# BtPluggy.net
KiCad netlist of a schematic drawn in EasyEDA Pro
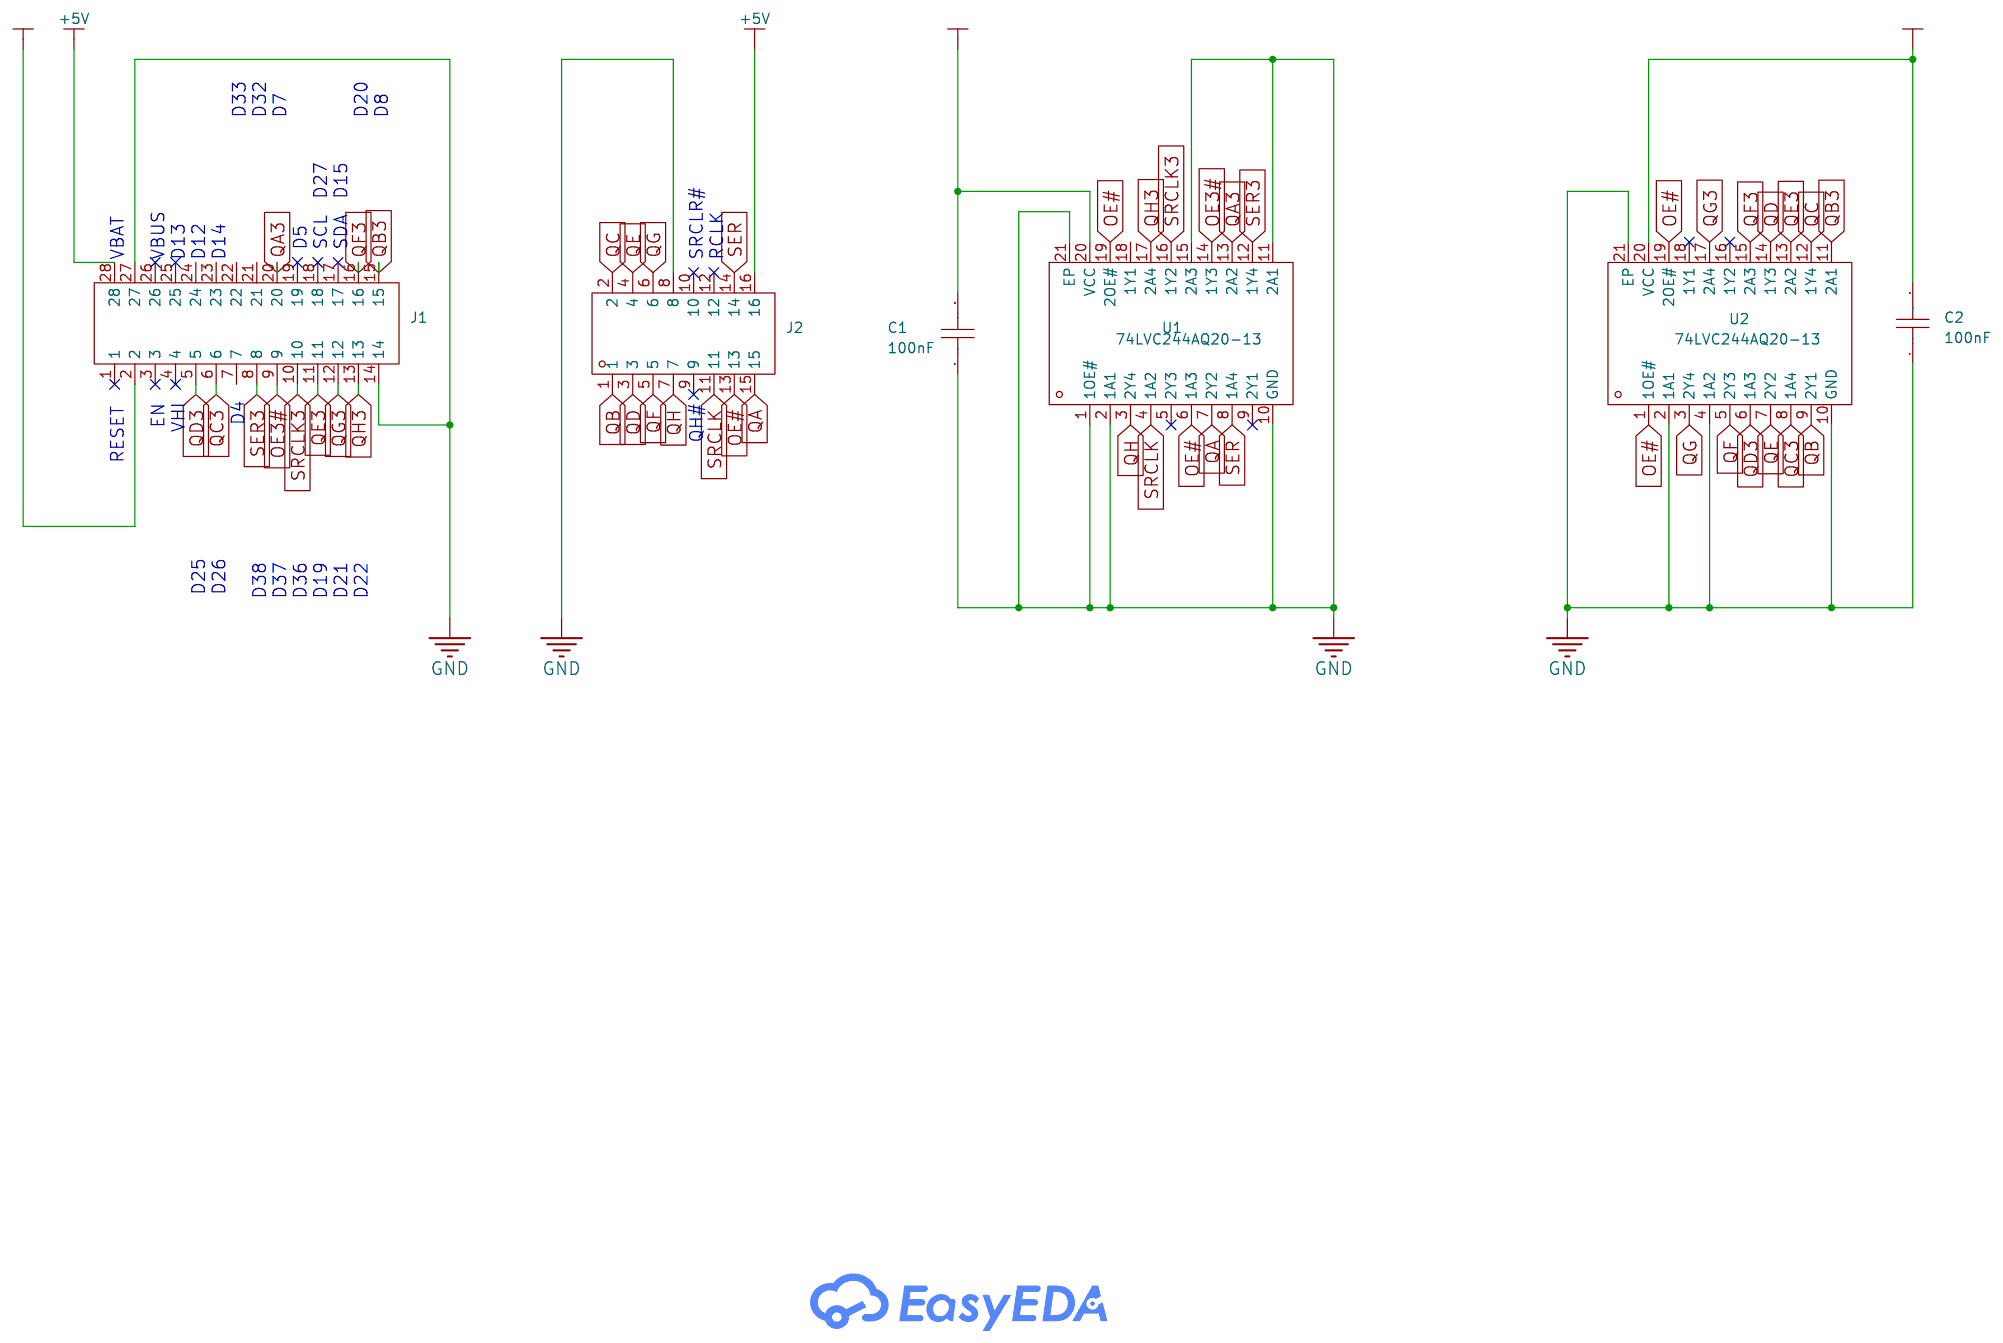
[diagram p0: schematic sheet]

(export (version "E")
  (design (tool "Eeschema 10.0.6"))
  (components
    (comp (ref "C1")
      (value "100nF")
      (footprint "easyedapro:C0402")
      (description "Capacitance:100nF Tolerance:±10% Tolerance:±10% Voltage Rating:16V Temperature Coefficient:X7R")
      (fields
        (field (name "Manufacturer Part") "CL05B104KO5NNNC")
        (field (name "Manufacturer") "SAMSUNG(三星)")
      )
      (libsource (lib "easyedapro") (part "CL05B104KO5NNNC"))
    )
    (comp (ref "C2")
      (value "100nF")
      (footprint "easyedapro:C0402")
      (description "Capacitance:100nF Tolerance:±10% Tolerance:±10% Voltage Rating:16V Temperature Coefficient:X7R")
      (fields
        (field (name "Manufacturer Part") "CL05B104KO5NNNC")
        (field (name "Manufacturer") "SAMSUNG(三星)")
      )
      (libsource (lib "easyedapro") (part "CL05B104KO5NNNC"))
    )
    (comp (ref "J1")
      (value "100-286-100-1001-00")
      (footprint "easyedapro:DIP-28_L35.5-W17.7-P2.54-LS15.2-BL-D0.8")
      (fields (field (name "Manufacturer Part") "28-6501-21") (field (name "Manufacturer") "Aries"))
      (libsource (lib "easyedapro") (part "28-6501-21"))
    )
    (comp (ref "J2")
      (value "Z-100163200100100")
      (footprint "easyedapro:CONN-SMD_16P-P2.54_X5621FVS-2X08-C1524D1988")
      (fields
        (field (name "Manufacturer Part") "X5621FVS-2x08-C1524D1988")
        (field (name "Manufacturer") "XKB Connectivity(中国星坤)")
      )
      (libsource (lib "easyedapro") (part "X5621FVS-2X08-C1524D1988"))
    )
    (comp (ref "U1")
      (value "74LVC244AQ20-13")
      (footprint "easyedapro:V-QFN4525-20_L4.5-W2.5-P0.50-BL")
      (fields (field (name "Manufacturer") "DIODES(美台)"))
      (libsource (lib "easyedapro") (part "74LVC244AQ20-13"))
    )
    (comp (ref "U2")
      (value "74LVC244AQ20-13")
      (footprint "easyedapro:V-QFN4525-20_L4.5-W2.5-P0.50-BL")
      (fields (field (name "Manufacturer") "DIODES(美台)"))
      (libsource (lib "easyedapro") (part "74LVC244AQ20-13"))
    )
  )
  (nets
    (net (code "1") (name "+5V") (class "Default")
      (node (ref "J1") (pin "28") (pinfunction "28_28") (pintype "unspecified"))
      (node (ref "J2") (pin "16") (pinfunction "16_16") (pintype "unspecified"))
    )
    (net (code "2") (name "GND") (class "Default")
      (node (ref "C1") (pin "1") (pinfunction "1_1") (pintype "unspecified"))
      (node (ref "C2") (pin "1") (pinfunction "1_1") (pintype "unspecified"))
      (node (ref "J1") (pin "14") (pinfunction "14_14") (pintype "unspecified"))
      (node (ref "J1") (pin "27") (pinfunction "27_27") (pintype "unspecified"))
      (node (ref "J2") (pin "8") (pinfunction "8_8") (pintype "unspecified"))
      (node (ref "U1") (pin "1") (pinfunction "1OE#_1") (pintype "unspecified"))
      (node (ref "U1") (pin "10") (pinfunction "GND_10") (pintype "unspecified"))
      (node (ref "U1") (pin "11") (pinfunction "2A1_11") (pintype "unspecified"))
      (node (ref "U1") (pin "15") (pinfunction "2A3_15") (pintype "unspecified"))
      (node (ref "U1") (pin "2") (pinfunction "1A1_2") (pintype "unspecified"))
      (node (ref "U1") (pin "21") (pinfunction "EP_21") (pintype "unspecified"))
      (node (ref "U2") (pin "10") (pinfunction "GND_10") (pintype "unspecified"))
      (node (ref "U2") (pin "2") (pinfunction "1A1_2") (pintype "unspecified"))
      (node (ref "U2") (pin "21") (pinfunction "EP_21") (pintype "unspecified"))
      (node (ref "U2") (pin "4") (pinfunction "1A2_4") (pintype "unspecified"))
    )
    (net (code "3") (name "OE#") (class "Default")
      (node (ref "J2") (pin "13") (pinfunction "13_13") (pintype "unspecified"))
      (node (ref "U1") (pin "19") (pinfunction "2OE#_19") (pintype "unspecified"))
      (node (ref "U1") (pin "6") (pinfunction "1A3_6") (pintype "unspecified"))
      (node (ref "U2") (pin "1") (pinfunction "1OE#_1") (pintype "unspecified"))
      (node (ref "U2") (pin "19") (pinfunction "2OE#_19") (pintype "unspecified"))
    )
    (net (code "4") (name "OE3#") (class "Default")
      (node (ref "J1") (pin "9") (pinfunction "9_9") (pintype "unspecified"))
      (node (ref "U1") (pin "14") (pinfunction "1Y3_14") (pintype "unspecified"))
    )
    (net (code "5") (name "QA") (class "Default")
      (node (ref "J2") (pin "15") (pinfunction "15_15") (pintype "unspecified"))
      (node (ref "U1") (pin "7") (pinfunction "2Y2_7") (pintype "unspecified"))
    )
    (net (code "6") (name "QA3") (class "Default")
      (node (ref "J1") (pin "20") (pinfunction "20_20") (pintype "unspecified"))
      (node (ref "U1") (pin "13") (pinfunction "2A2_13") (pintype "unspecified"))
    )
    (net (code "7") (name "QB") (class "Default")
      (node (ref "J2") (pin "1") (pinfunction "1_1") (pintype "unspecified"))
      (node (ref "U2") (pin "9") (pinfunction "2Y1_9") (pintype "unspecified"))
    )
    (net (code "8") (name "QB3") (class "Default")
      (node (ref "J1") (pin "15") (pinfunction "15_15") (pintype "unspecified"))
      (node (ref "U2") (pin "11") (pinfunction "2A1_11") (pintype "unspecified"))
    )
    (net (code "9") (name "QC") (class "Default")
      (node (ref "J2") (pin "2") (pinfunction "2_2") (pintype "unspecified"))
      (node (ref "U2") (pin "12") (pinfunction "1Y4_12") (pintype "unspecified"))
    )
    (net (code "10") (name "QC3") (class "Default")
      (node (ref "J1") (pin "6") (pinfunction "6_6") (pintype "unspecified"))
      (node (ref "U2") (pin "8") (pinfunction "1A4_8") (pintype "unspecified"))
    )
    (net (code "11") (name "QD") (class "Default")
      (node (ref "J2") (pin "3") (pinfunction "3_3") (pintype "unspecified"))
      (node (ref "U2") (pin "14") (pinfunction "1Y3_14") (pintype "unspecified"))
    )
    (net (code "12") (name "QD3") (class "Default")
      (node (ref "J1") (pin "5") (pinfunction "5_5") (pintype "unspecified"))
      (node (ref "U2") (pin "6") (pinfunction "1A3_6") (pintype "unspecified"))
    )
    (net (code "13") (name "QE") (class "Default")
      (node (ref "J2") (pin "4") (pinfunction "4_4") (pintype "unspecified"))
      (node (ref "U2") (pin "7") (pinfunction "2Y2_7") (pintype "unspecified"))
    )
    (net (code "14") (name "QE3") (class "Default")
      (node (ref "J1") (pin "11") (pinfunction "11_11") (pintype "unspecified"))
      (node (ref "U2") (pin "13") (pinfunction "2A2_13") (pintype "unspecified"))
    )
    (net (code "15") (name "QF") (class "Default")
      (node (ref "J2") (pin "5") (pinfunction "5_5") (pintype "unspecified"))
      (node (ref "U2") (pin "5") (pinfunction "2Y3_5") (pintype "unspecified"))
    )
    (net (code "16") (name "QF3") (class "Default")
      (node (ref "J1") (pin "16") (pinfunction "16_16") (pintype "unspecified"))
      (node (ref "U2") (pin "15") (pinfunction "2A3_15") (pintype "unspecified"))
    )
    (net (code "17") (name "QG") (class "Default")
      (node (ref "J2") (pin "6") (pinfunction "6_6") (pintype "unspecified"))
      (node (ref "U2") (pin "3") (pinfunction "2Y4_3") (pintype "unspecified"))
    )
    (net (code "18") (name "QG3") (class "Default")
      (node (ref "J1") (pin "12") (pinfunction "12_12") (pintype "unspecified"))
      (node (ref "U2") (pin "17") (pinfunction "2A4_17") (pintype "unspecified"))
    )
    (net (code "19") (name "QH") (class "Default")
      (node (ref "J2") (pin "7") (pinfunction "7_7") (pintype "unspecified"))
      (node (ref "U1") (pin "3") (pinfunction "2Y4_3") (pintype "unspecified"))
    )
    (net (code "20") (name "QH3") (class "Default")
      (node (ref "J1") (pin "13") (pinfunction "13_13") (pintype "unspecified"))
      (node (ref "U1") (pin "17") (pinfunction "2A4_17") (pintype "unspecified"))
    )
    (net (code "21") (name "SER") (class "Default")
      (node (ref "J2") (pin "14") (pinfunction "14_14") (pintype "unspecified"))
      (node (ref "U1") (pin "8") (pinfunction "1A4_8") (pintype "unspecified"))
    )
    (net (code "22") (name "SER3") (class "Default")
      (node (ref "J1") (pin "8") (pinfunction "8_8") (pintype "unspecified"))
      (node (ref "U1") (pin "12") (pinfunction "1Y4_12") (pintype "unspecified"))
    )
    (net (code "23") (name "SRCLK") (class "Default")
      (node (ref "J2") (pin "11") (pinfunction "11_11") (pintype "unspecified"))
      (node (ref "U1") (pin "4") (pinfunction "1A2_4") (pintype "unspecified"))
    )
    (net (code "24") (name "SRCLK3") (class "Default")
      (node (ref "J1") (pin "10") (pinfunction "10_10") (pintype "unspecified"))
      (node (ref "U1") (pin "16") (pinfunction "1Y2_16") (pintype "unspecified"))
    )
    (net (code "25") (name "V33") (class "Default")
      (node (ref "C1") (pin "2") (pinfunction "2_2") (pintype "unspecified"))
      (node (ref "C2") (pin "2") (pinfunction "2_2") (pintype "unspecified"))
      (node (ref "J1") (pin "2") (pinfunction "2_2") (pintype "unspecified"))
      (node (ref "U1") (pin "20") (pinfunction "VCC_20") (pintype "unspecified"))
      (node (ref "U2") (pin "20") (pinfunction "VCC_20") (pintype "unspecified"))
    )
    (net (code "26") (name "unconnected-(J1-Pad1)") (class "Default")
      (node (ref "J1") (pin "1") (pinfunction "1_1") (pintype "unspecified+no_connect"))
    )
    (net (code "27") (name "unconnected-(J1-Pad3)") (class "Default")
      (node (ref "J1") (pin "3") (pinfunction "3_3") (pintype "unspecified+no_connect"))
    )
    (net (code "28") (name "unconnected-(J1-Pad4)") (class "Default")
      (node (ref "J1") (pin "4") (pinfunction "4_4") (pintype "unspecified+no_connect"))
    )
    (net (code "29") (name "unconnected-(J1-Pad7)") (class "Default")
      (node (ref "J1") (pin "7") (pinfunction "7_7") (pintype "unspecified"))
    )
    (net (code "30") (name "unconnected-(J1-Pad17)") (class "Default")
      (node (ref "J1") (pin "17") (pinfunction "17_17") (pintype "unspecified+no_connect"))
    )
    (net (code "31") (name "unconnected-(J1-Pad18)") (class "Default")
      (node (ref "J1") (pin "18") (pinfunction "18_18") (pintype "unspecified+no_connect"))
    )
    (net (code "32") (name "unconnected-(J1-Pad19)") (class "Default")
      (node (ref "J1") (pin "19") (pinfunction "19_19") (pintype "unspecified+no_connect"))
    )
    (net (code "33") (name "unconnected-(J1-Pad21)") (class "Default")
      (node (ref "J1") (pin "21") (pinfunction "21_21") (pintype "unspecified"))
    )
    (net (code "34") (name "unconnected-(J1-Pad22)") (class "Default")
      (node (ref "J1") (pin "22") (pinfunction "22_22") (pintype "unspecified"))
    )
    (net (code "35") (name "unconnected-(J1-Pad23)") (class "Default")
      (node (ref "J1") (pin "23") (pinfunction "23_23") (pintype "unspecified"))
    )
    (net (code "36") (name "unconnected-(J1-Pad24)") (class "Default")
      (node (ref "J1") (pin "24") (pinfunction "24_24") (pintype "unspecified"))
    )
    (net (code "37") (name "unconnected-(J1-Pad25)") (class "Default")
      (node (ref "J1") (pin "25") (pinfunction "25_25") (pintype "unspecified+no_connect"))
    )
    (net (code "38") (name "unconnected-(J1-Pad26)") (class "Default")
      (node (ref "J1") (pin "26") (pinfunction "26_26") (pintype "unspecified+no_connect"))
    )
    (net (code "39") (name "unconnected-(J2-Pad9)") (class "Default")
      (node (ref "J2") (pin "9") (pinfunction "9_9") (pintype "unspecified+no_connect"))
    )
    (net (code "40") (name "unconnected-(J2-Pad10)") (class "Default")
      (node (ref "J2") (pin "10") (pinfunction "10_10") (pintype "unspecified+no_connect"))
    )
    (net (code "41") (name "unconnected-(J2-Pad12)") (class "Default")
      (node (ref "J2") (pin "12") (pinfunction "12_12") (pintype "unspecified+no_connect"))
    )
    (net (code "42") (name "unconnected-(U1-1Y1-Pad18)") (class "Default")
      (node (ref "U1") (pin "18") (pinfunction "1Y1_18") (pintype "unspecified"))
    )
    (net (code "43") (name "unconnected-(U1-2Y1-Pad9)") (class "Default")
      (node (ref "U1") (pin "9") (pinfunction "2Y1_9") (pintype "unspecified+no_connect"))
    )
    (net (code "44") (name "unconnected-(U1-2Y3-Pad5)") (class "Default")
      (node (ref "U1") (pin "5") (pinfunction "2Y3_5") (pintype "unspecified+no_connect"))
    )
    (net (code "45") (name "unconnected-(U2-1Y1-Pad18)") (class "Default")
      (node (ref "U2") (pin "18") (pinfunction "1Y1_18") (pintype "unspecified+no_connect"))
    )
    (net (code "46") (name "unconnected-(U2-1Y2-Pad16)") (class "Default")
      (node (ref "U2") (pin "16") (pinfunction "1Y2_16") (pintype "unspecified+no_connect"))
    )
  )
)
